# I_DC_Buffering.net
KiCad netlist of a schematic drawn in Altium Designer
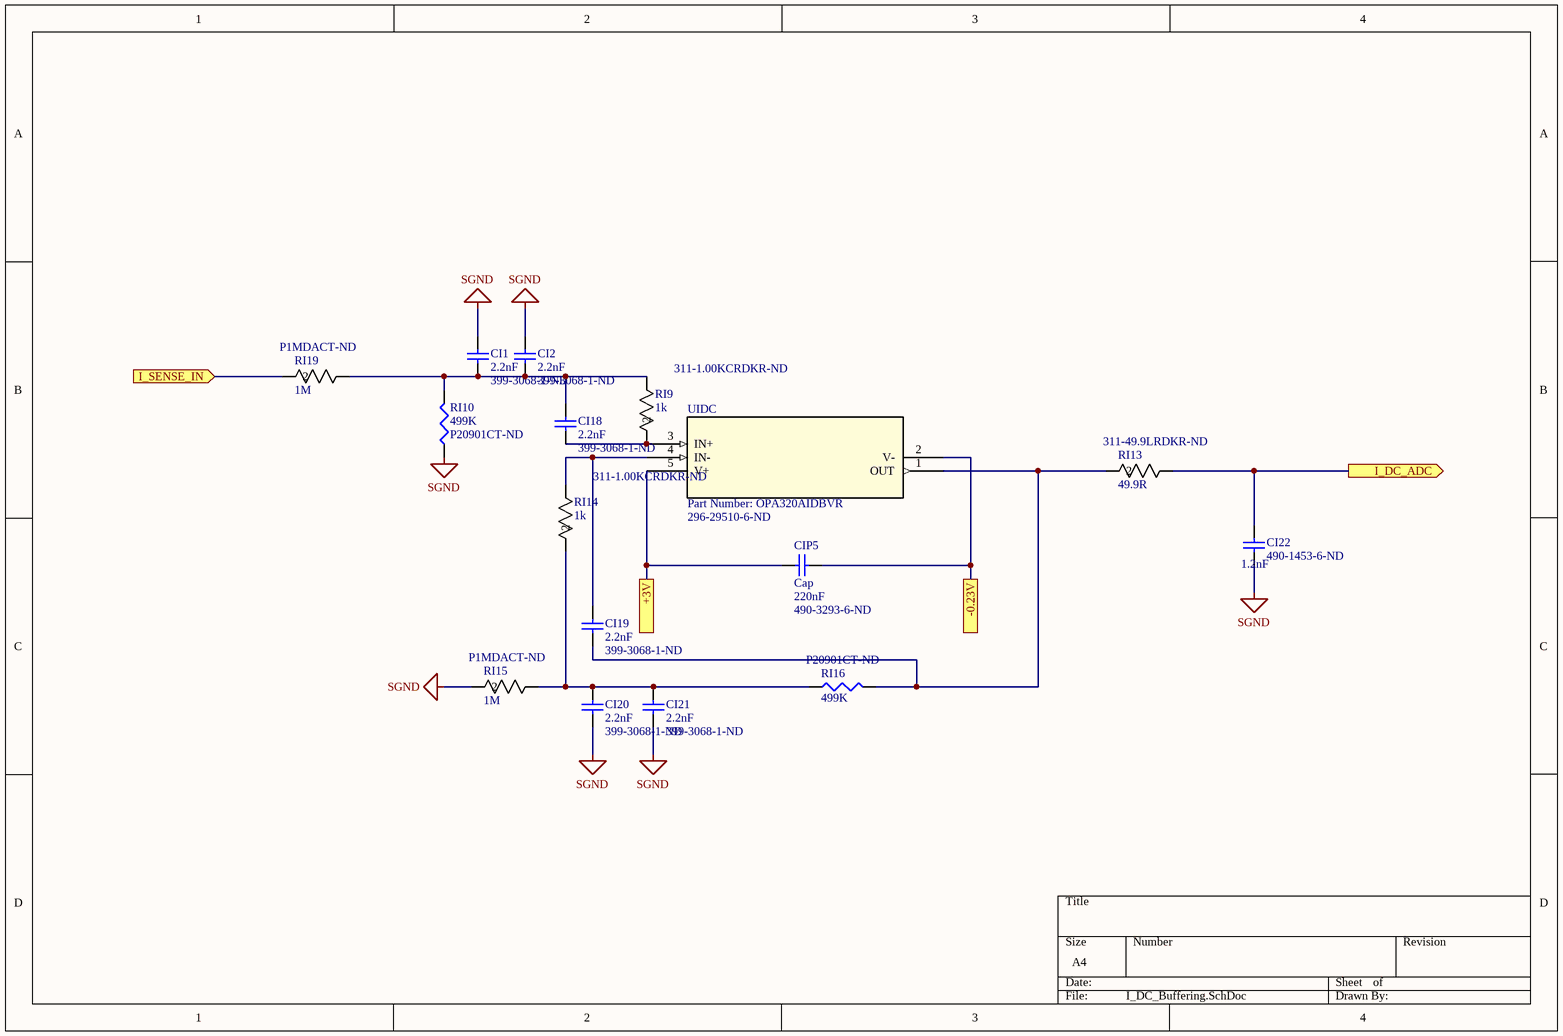
[diagram p0: I_DC_Buffering.SchDoc]

(export (version "E")
  (design (tool "Eeschema 10.0.6"))
  (components
    (comp (ref "CI1")
      (value "2.2nF")
      (footprint "0402")
      (fields
        (field (name "SUPPLIER PART NUMBER 1") "399-3068-1-ND")
        (field (name "MANUFACTURER") "KEMET")
        (field (name "MANUFACTURER PART NUMBER") "C0402C222K5RACTU")
        (field (name "TOLERANCE") "10%")
        (field (name "PUBLISHER") "Altium Limited")
      )
      (libsource (lib "Miscellaneous Devices") (part "Cap Semi"))
    )
    (comp (ref "CI2")
      (value "2.2nF")
      (footprint "0402")
      (fields
        (field (name "SUPPLIER PART NUMBER 1") "399-3068-1-ND")
        (field (name "MANUFACTURER") "KEMET")
        (field (name "MANUFACTURER PART NUMBER") "C0402C222K5RACTU")
        (field (name "TOLERANCE") "10%")
        (field (name "PUBLISHER") "Altium Limited")
      )
      (libsource (lib "Miscellaneous Devices") (part "Cap Semi"))
    )
    (comp (ref "CI18")
      (value "2.2nF")
      (footprint "0402")
      (fields
        (field (name "SUPPLIER PART NUMBER 1") "399-3068-1-ND")
        (field (name "MANUFACTURER") "KEMET")
        (field (name "MANUFACTURER PART NUMBER") "C0402C222K5RACTU")
        (field (name "TOLERANCE") "10%")
        (field (name "PUBLISHER") "Altium Limited")
      )
      (libsource (lib "Miscellaneous Devices") (part "Cap Semi"))
    )
    (comp (ref "CI19")
      (value "2.2nF")
      (footprint "0402")
      (fields
        (field (name "SUPPLIER PART NUMBER 1") "399-3068-1-ND")
        (field (name "MANUFACTURER") "KEMET")
        (field (name "MANUFACTURER PART NUMBER") "C0402C222K5RACTU")
        (field (name "TOLERANCE") "10%")
        (field (name "PUBLISHER") "Altium Limited")
      )
      (libsource (lib "Miscellaneous Devices") (part "Cap Semi"))
    )
    (comp (ref "CI20")
      (value "2.2nF")
      (footprint "0402")
      (fields
        (field (name "SUPPLIER PART NUMBER 1") "399-3068-1-ND")
        (field (name "MANUFACTURER") "KEMET")
        (field (name "MANUFACTURER PART NUMBER") "C0402C222K5RACTU")
        (field (name "TOLERANCE") "10%")
        (field (name "PUBLISHER") "Altium Limited")
      )
      (libsource (lib "Miscellaneous Devices") (part "Cap Semi"))
    )
    (comp (ref "CI21")
      (value "2.2nF")
      (footprint "0402")
      (fields
        (field (name "SUPPLIER PART NUMBER 1") "399-3068-1-ND")
        (field (name "MANUFACTURER") "KEMET")
        (field (name "MANUFACTURER PART NUMBER") "C0402C222K5RACTU")
        (field (name "TOLERANCE") "10%")
        (field (name "PUBLISHER") "Altium Limited")
      )
      (libsource (lib "Miscellaneous Devices") (part "Cap Semi"))
    )
    (comp (ref "CI22")
      (value "1.2nF")
      (footprint "G-188")
      (fields
        (field (name "SUPPLIER PART NUMBER 1") "490-1453-6-ND")
        (field (name "MANUFACTURER") "Murata")
        (field (name "MANUFACTURER PART NUMBER") "GRM1885C1H122JA01D")
        (field (name "TOLERANCE") "5%")
      )
      (libsource (lib "Embest") (part "C"))
    )
    (comp (ref "CIP5")
      (value "Cap")
      (footprint "G-188")
      (description "Capacitor")
      (fields
        (field (name "ALTIUM_VALUE") "220nF")
        (field (name "SUPPLIER PART NUMBER 1") "490-3293-6-ND")
        (field (name "MANUFACTURER") "Murata")
        (field (name "MANUFACTURER PART NUMBER") "GRM188R71C224KA01D")
        (field (name "PUBLISHER") "Altium Limited")
      )
      (libsource (lib "Miscellaneous Devices") (part "Cap"))
    )
    (comp (ref "RI9")
      (value "1k")
      (footprint "RC0805N")
      (description "No Description Available")
      (fields
        (field (name "MANUFACTURER_PART_NUMBER") "RC0805FR-071KL")
        (field (name "SUPPLIER PART NUMBER 1") "311-1.00KCRDKR-ND")
        (field (name "MANUFACTURER") "Yageo")
        (field (name "COPYRIGHT") "Copyright (C) 2018 Accelerated Designs. All rights reserved")
      )
      (libsource (lib "RC0805FR071KL") (part "RC0805FR-071KL"))
    )
    (comp (ref "RI10")
      (value "499K")
      (footprint "6-0805_N")
      (description "Resistor")
      (fields
        (field (name "SUPPLIER PART NUMBER 1") "P20901CT-ND")
        (field (name "MANUFACTURER") "Panasonic")
        (field (name "MANUFACTURER PART NUMBER") "ERJ-PB6B4993V")
        (field (name "PUBLISHER") "Altium Limited")
      )
      (libsource (lib "Miscellaneous Devices") (part "Res3"))
    )
    (comp (ref "RI13")
      (value "49.9R")
      (footprint "RC0402N")
      (description "No Description Available")
      (fields
        (field (name "MANUFACTURER_PART_NUMBER") "RC0402FR-0749R9L")
        (field (name "SUPPLIER PART NUMBER 1") "311-49.9LRDKR-ND")
        (field (name "MANUFACTURER") "Yageo")
        (field (name "COPYRIGHT") "Copyright (C) 2018 Accelerated Designs. All rights reserved")
      )
      (libsource (lib "RC0402FR0749R9L") (part "RC0402FR-0749R9L"))
    )
    (comp (ref "RI14")
      (value "1k")
      (footprint "RC0805N")
      (description "No Description Available")
      (fields
        (field (name "MANUFACTURER_PART_NUMBER") "RC0805FR-071KL")
        (field (name "SUPPLIER PART NUMBER 1") "311-1.00KCRDKR-ND")
        (field (name "MANUFACTURER") "Yageo")
        (field (name "COPYRIGHT") "Copyright (C) 2018 Accelerated Designs. All rights reserved")
      )
      (libsource (lib "RC0805FR071KL") (part "RC0805FR-071KL"))
    )
    (comp (ref "RI15")
      (value "1M")
      (footprint "RC0805N")
      (description "No Description Available")
      (fields
        (field (name "MANUFACTURER_PART_NUMBER") "ERA-6AEB105V")
        (field (name "SUPPLIER PART NUMBER 1") "P1MDACT-ND")
        (field (name "MANUFACTURER") "Panasonic")
        (field (name "COPYRIGHT") "Copyright (C) 2018 Accelerated Designs. All rights reserved")
      )
      (libsource (lib "ERA-6AEB105V") (part "ERA-6AEB105V"))
    )
    (comp (ref "RI16")
      (value "499K")
      (footprint "6-0805_N")
      (description "Resistor")
      (fields
        (field (name "SUPPLIER PART NUMBER 1") "P20901CT-ND")
        (field (name "MANUFACTURER") "Panasonic")
        (field (name "MANUFACTURER PART NUMBER") "ERJ-PB6B4993V")
        (field (name "PUBLISHER") "Altium Limited")
      )
      (libsource (lib "Miscellaneous Devices") (part "Res3"))
    )
    (comp (ref "RI19")
      (value "1M")
      (footprint "RC0805N")
      (description "No Description Available")
      (fields
        (field (name "MANUFACTURER_PART_NUMBER") "ERA-6AEB105V")
        (field (name "SUPPLIER PART NUMBER 1") "P1MDACT-ND")
        (field (name "MANUFACTURER") "Panasonic")
        (field (name "COPYRIGHT") "Copyright (C) 2018 Accelerated Designs. All rights reserved")
      )
      (libsource (lib "ERA-6AEB105V") (part "ERA-6AEB105V"))
    )
    (comp (ref "UIDC")
      (value "Part Number: OPA320AIDBVR")
      (footprint "DBV5")
      (description "No Description Available")
      (fields
        (field (name "SUPPLIER PART NUMBER 1") "296-29510-6-ND")
        (field (name "MANUFACTURER") "Texas Instruments")
        (field (name "MANUFACTURER PART NUMBER") "OPA320AIDBVT")
      )
      (libsource (lib "OPA320SAIDBVR") (part "OPA320SAIDBVR"))
    )
  )
  (nets
    (net (code "1") (name "/+3V") (class "Default")
      (node (ref "CIP5") (pin "2") (pinfunction "2_2") (pintype "passive"))
      (node (ref "UIDC") (pin "5") (pinfunction "V+_5") (pintype "power_in"))
    )
    (net (code "2") (name "/-0.23V") (class "Default")
      (node (ref "CIP5") (pin "1") (pinfunction "1_1") (pintype "passive"))
      (node (ref "UIDC") (pin "2") (pinfunction "V-_2") (pintype "power_in"))
    )
    (net (code "3") (name "/I_DC_ADC") (class "Default")
      (node (ref "CI22") (pin "1") (pinfunction "1_1") (pintype "passive"))
      (node (ref "RI13") (pin "1") (pinfunction "1_1") (pintype "passive"))
    )
    (net (code "4") (name "/I_SENSE_IN") (class "Default")
      (node (ref "RI19") (pin "2") (pinfunction "2_2") (pintype "passive"))
    )
    (net (code "5") (name "Net-(CI1-Pad1)") (class "Default")
      (node (ref "CI1") (pin "1") (pinfunction "1_1") (pintype "passive"))
      (node (ref "CI18") (pin "1") (pinfunction "1_1") (pintype "passive"))
      (node (ref "CI2") (pin "1") (pinfunction "1_1") (pintype "passive"))
      (node (ref "RI10") (pin "2") (pinfunction "2_2") (pintype "passive"))
      (node (ref "RI19") (pin "1") (pinfunction "1_1") (pintype "passive"))
      (node (ref "RI9") (pin "1") (pinfunction "1_1") (pintype "passive"))
    )
    (net (code "6") (name "Net-(CI20-Pad1)") (class "Default")
      (node (ref "CI20") (pin "1") (pinfunction "1_1") (pintype "passive"))
      (node (ref "CI21") (pin "1") (pinfunction "1_1") (pintype "passive"))
      (node (ref "RI14") (pin "2") (pinfunction "2_2") (pintype "passive"))
      (node (ref "RI15") (pin "1") (pinfunction "1_1") (pintype "passive"))
      (node (ref "RI16") (pin "1") (pinfunction "1_1") (pintype "passive"))
    )
    (net (code "7") (name "Net-(UIDC-IN+)") (class "Default")
      (node (ref "CI18") (pin "2") (pinfunction "2_2") (pintype "passive"))
      (node (ref "RI9") (pin "2") (pinfunction "2_2") (pintype "passive"))
      (node (ref "UIDC") (pin "3") (pinfunction "IN+_3") (pintype "input"))
    )
    (net (code "8") (name "Net-(UIDC-IN-)") (class "Default")
      (node (ref "CI19") (pin "1") (pinfunction "1_1") (pintype "passive"))
      (node (ref "RI14") (pin "1") (pinfunction "1_1") (pintype "passive"))
      (node (ref "UIDC") (pin "4") (pinfunction "IN-_4") (pintype "input"))
    )
    (net (code "9") (name "Net-(UIDC-OUT)") (class "Default")
      (node (ref "CI19") (pin "2") (pinfunction "2_2") (pintype "passive"))
      (node (ref "RI13") (pin "2") (pinfunction "2_2") (pintype "passive"))
      (node (ref "RI16") (pin "2") (pinfunction "2_2") (pintype "passive"))
      (node (ref "UIDC") (pin "1") (pinfunction "OUT_1") (pintype "output"))
    )
    (net (code "10") (name "SGND") (class "Default")
      (node (ref "CI1") (pin "2") (pinfunction "2_2") (pintype "passive"))
      (node (ref "CI2") (pin "2") (pinfunction "2_2") (pintype "passive"))
      (node (ref "CI20") (pin "2") (pinfunction "2_2") (pintype "passive"))
      (node (ref "CI21") (pin "2") (pinfunction "2_2") (pintype "passive"))
      (node (ref "CI22") (pin "2") (pinfunction "2_2") (pintype "passive"))
      (node (ref "RI10") (pin "1") (pinfunction "1_1") (pintype "passive"))
      (node (ref "RI15") (pin "2") (pinfunction "2_2") (pintype "passive"))
    )
  )
)
